# RoboCore_Light_sensor_bar.net
KiCad netlist of a schematic drawn in EAGLE
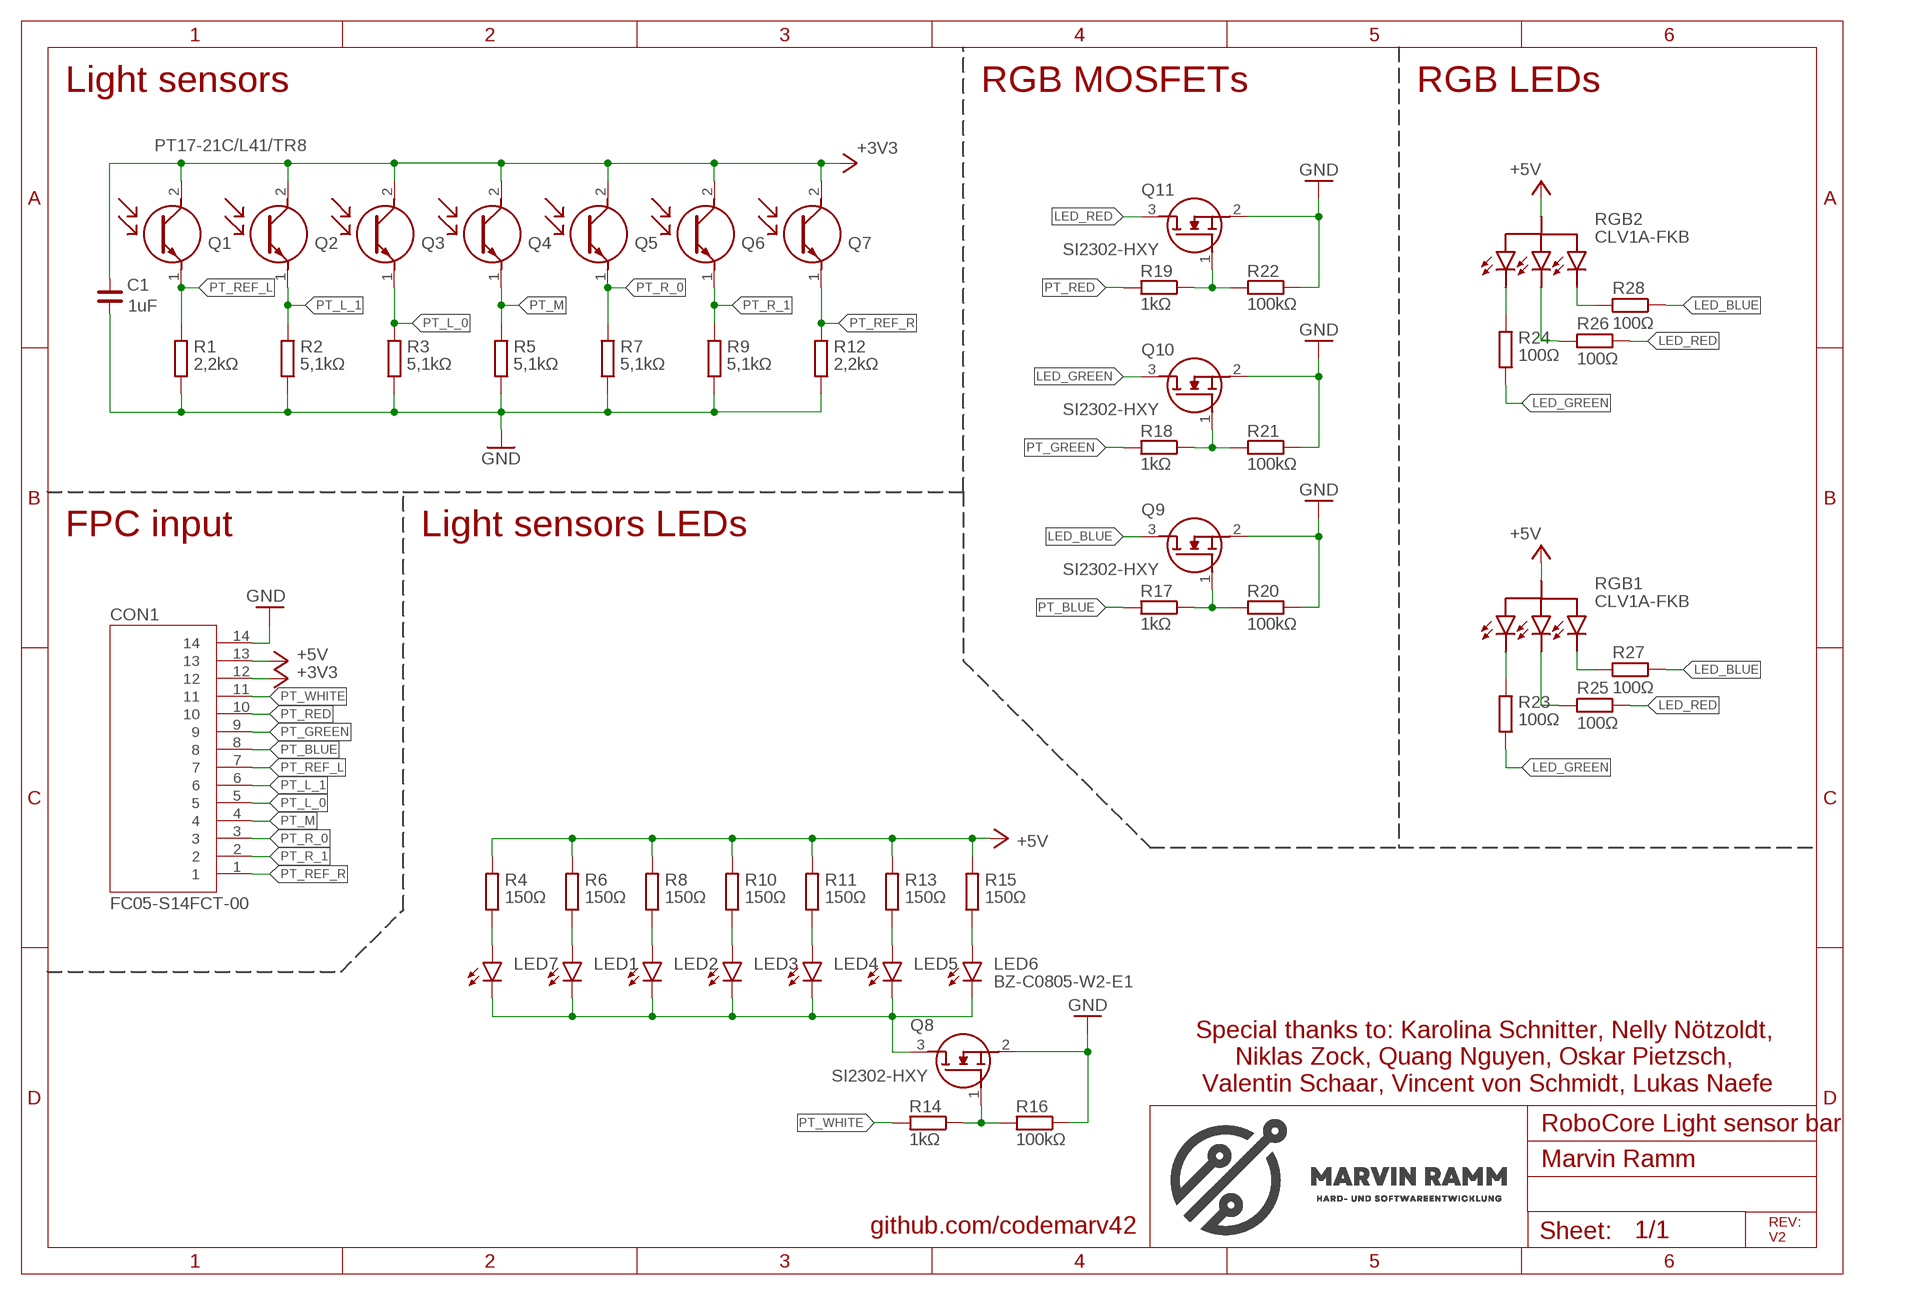
[diagram p0: schematic, sheet 1]

(export (version "E")
  (design (tool "Eeschema 10.0.6"))
  (components
    (comp (ref "C1")
      (value "1uF")
      (footprint "eagle-import:C0402")
      (libsource (lib "eagle-import") (part "C_0402"))
    )
    (comp (ref "CON1")
      (value "FC05-S14FCT-00")
      (footprint "eagle-import:FC05-S14FCT-00")
      (libsource (lib "eagle-import") (part "FC05-S14FCT-00"))
    )
    (comp (ref "LED1")
      (value "LEDCHIP-LED0805")
      (footprint "eagle-import:CHIP-LED0805")
      (libsource (lib "eagle-import") (part "LEDCHIP-LED0805"))
    )
    (comp (ref "LED2")
      (value "LEDCHIP-LED0805")
      (footprint "eagle-import:CHIP-LED0805")
      (libsource (lib "eagle-import") (part "LEDCHIP-LED0805"))
    )
    (comp (ref "LED3")
      (value "LEDCHIP-LED0805")
      (footprint "eagle-import:CHIP-LED0805")
      (libsource (lib "eagle-import") (part "LEDCHIP-LED0805"))
    )
    (comp (ref "LED4")
      (value "LEDCHIP-LED0805")
      (footprint "eagle-import:CHIP-LED0805")
      (libsource (lib "eagle-import") (part "LEDCHIP-LED0805"))
    )
    (comp (ref "LED5")
      (value "LEDCHIP-LED0805")
      (footprint "eagle-import:CHIP-LED0805")
      (libsource (lib "eagle-import") (part "LEDCHIP-LED0805"))
    )
    (comp (ref "LED6")
      (value "LEDCHIP-LED0805")
      (footprint "eagle-import:CHIP-LED0805")
      (libsource (lib "eagle-import") (part "LEDCHIP-LED0805"))
    )
    (comp (ref "LED7")
      (value "LEDCHIP-LED0805")
      (footprint "eagle-import:CHIP-LED0805")
      (libsource (lib "eagle-import") (part "LEDCHIP-LED0805"))
    )
    (comp (ref "Q1")
      (value "PT17-21C/L41/TR8")
      (footprint "eagle-import:0805")
      (libsource (lib "eagle-import") (part "PT17-21C/L41/TR8"))
    )
    (comp (ref "Q2")
      (value "PT17-21C/L41/TR8")
      (footprint "eagle-import:0805")
      (libsource (lib "eagle-import") (part "PT17-21C/L41/TR8"))
    )
    (comp (ref "Q3")
      (value "PT17-21C/L41/TR8")
      (footprint "eagle-import:0805")
      (libsource (lib "eagle-import") (part "PT17-21C/L41/TR8"))
    )
    (comp (ref "Q4")
      (value "PT17-21C/L41/TR8")
      (footprint "eagle-import:0805")
      (libsource (lib "eagle-import") (part "PT17-21C/L41/TR8"))
    )
    (comp (ref "Q5")
      (value "PT17-21C/L41/TR8")
      (footprint "eagle-import:0805")
      (libsource (lib "eagle-import") (part "PT17-21C/L41/TR8"))
    )
    (comp (ref "Q6")
      (value "PT17-21C/L41/TR8")
      (footprint "eagle-import:0805")
      (libsource (lib "eagle-import") (part "PT17-21C/L41/TR8"))
    )
    (comp (ref "Q7")
      (value "PT17-21C/L41/TR8")
      (footprint "eagle-import:0805")
      (libsource (lib "eagle-import") (part "PT17-21C/L41/TR8"))
    )
    (comp (ref "Q8")
      (value "SI2302DDS-T1-GE3")
      (footprint "eagle-import:SOT95P237X112-3N")
      (fields (field (name "MOUSER_PART_NUMBER") "78-SI2302DDS-T1-GE3"))
      (libsource (lib "eagle-import") (part "SI2302DDS-T1-GE3"))
    )
    (comp (ref "Q9")
      (value "SI2302DDS-T1-GE3")
      (footprint "eagle-import:SOT95P237X112-3N")
      (fields (field (name "MOUSER_PART_NUMBER") "78-SI2302DDS-T1-GE3"))
      (libsource (lib "eagle-import") (part "SI2302DDS-T1-GE3"))
    )
    (comp (ref "Q10")
      (value "SI2302DDS-T1-GE3")
      (footprint "eagle-import:SOT95P237X112-3N")
      (fields (field (name "MOUSER_PART_NUMBER") "78-SI2302DDS-T1-GE3"))
      (libsource (lib "eagle-import") (part "SI2302DDS-T1-GE3"))
    )
    (comp (ref "Q11")
      (value "SI2302DDS-T1-GE3")
      (footprint "eagle-import:SOT95P237X112-3N")
      (fields (field (name "MOUSER_PART_NUMBER") "78-SI2302DDS-T1-GE3"))
      (libsource (lib "eagle-import") (part "SI2302DDS-T1-GE3"))
    )
    (comp (ref "R1")
      (value "2,2kΩ")
      (footprint "eagle-import:R0402")
      (libsource (lib "eagle-import") (part "R_0402"))
    )
    (comp (ref "R2")
      (value "5,1kΩ")
      (footprint "eagle-import:R0402")
      (libsource (lib "eagle-import") (part "R_0402"))
    )
    (comp (ref "R3")
      (value "5,1kΩ")
      (footprint "eagle-import:R0402")
      (libsource (lib "eagle-import") (part "R_0402"))
    )
    (comp (ref "R4")
      (value "150Ω")
      (footprint "eagle-import:R0402")
      (libsource (lib "eagle-import") (part "R_0402"))
    )
    (comp (ref "R5")
      (value "5,1kΩ")
      (footprint "eagle-import:R0402")
      (libsource (lib "eagle-import") (part "R_0402"))
    )
    (comp (ref "R6")
      (value "150Ω")
      (footprint "eagle-import:R0402")
      (libsource (lib "eagle-import") (part "R_0402"))
    )
    (comp (ref "R7")
      (value "5,1kΩ")
      (footprint "eagle-import:R0402")
      (libsource (lib "eagle-import") (part "R_0402"))
    )
    (comp (ref "R8")
      (value "150Ω")
      (footprint "eagle-import:R0402")
      (libsource (lib "eagle-import") (part "R_0402"))
    )
    (comp (ref "R9")
      (value "5,1kΩ")
      (footprint "eagle-import:R0402")
      (libsource (lib "eagle-import") (part "R_0402"))
    )
    (comp (ref "R10")
      (value "150Ω")
      (footprint "eagle-import:R0402")
      (libsource (lib "eagle-import") (part "R_0402"))
    )
    (comp (ref "R11")
      (value "150Ω")
      (footprint "eagle-import:R0402")
      (libsource (lib "eagle-import") (part "R_0402"))
    )
    (comp (ref "R12")
      (value "2,2kΩ")
      (footprint "eagle-import:R0402")
      (libsource (lib "eagle-import") (part "R_0402"))
    )
    (comp (ref "R13")
      (value "150Ω")
      (footprint "eagle-import:R0402")
      (libsource (lib "eagle-import") (part "R_0402"))
    )
    (comp (ref "R14")
      (value "1kΩ")
      (footprint "eagle-import:R0402")
      (libsource (lib "eagle-import") (part "R_0402"))
    )
    (comp (ref "R15")
      (value "150Ω")
      (footprint "eagle-import:R0402")
      (libsource (lib "eagle-import") (part "R_0402"))
    )
    (comp (ref "R16")
      (value "100kΩ")
      (footprint "eagle-import:R0402")
      (libsource (lib "eagle-import") (part "R_0402"))
    )
    (comp (ref "R17")
      (value "1kΩ")
      (footprint "eagle-import:R0402")
      (libsource (lib "eagle-import") (part "R_0402"))
    )
    (comp (ref "R18")
      (value "1kΩ")
      (footprint "eagle-import:R0402")
      (libsource (lib "eagle-import") (part "R_0402"))
    )
    (comp (ref "R19")
      (value "1kΩ")
      (footprint "eagle-import:R0402")
      (libsource (lib "eagle-import") (part "R_0402"))
    )
    (comp (ref "R20")
      (value "100kΩ")
      (footprint "eagle-import:R0402")
      (libsource (lib "eagle-import") (part "R_0402"))
    )
    (comp (ref "R21")
      (value "100kΩ")
      (footprint "eagle-import:R0402")
      (libsource (lib "eagle-import") (part "R_0402"))
    )
    (comp (ref "R22")
      (value "100kΩ")
      (footprint "eagle-import:R0402")
      (libsource (lib "eagle-import") (part "R_0402"))
    )
    (comp (ref "R23")
      (value "100Ω")
      (footprint "eagle-import:R0402")
      (libsource (lib "eagle-import") (part "R_0402"))
    )
    (comp (ref "R24")
      (value "100Ω")
      (footprint "eagle-import:R0402")
      (libsource (lib "eagle-import") (part "R_0402"))
    )
    (comp (ref "R25")
      (value "100Ω")
      (footprint "eagle-import:R0402")
      (libsource (lib "eagle-import") (part "R_0402"))
    )
    (comp (ref "R26")
      (value "100Ω")
      (footprint "eagle-import:R0402")
      (libsource (lib "eagle-import") (part "R_0402"))
    )
    (comp (ref "R27")
      (value "100Ω")
      (footprint "eagle-import:R0402")
      (libsource (lib "eagle-import") (part "R_0402"))
    )
    (comp (ref "R28")
      (value "100Ω")
      (footprint "eagle-import:R0402")
      (libsource (lib "eagle-import") (part "R_0402"))
    )
    (comp (ref "RGB1")
      (value "RGBLED")
      (footprint "eagle-import:RGBLED")
      (libsource (lib "eagle-import") (part "RGBLED"))
    )
    (comp (ref "RGB2")
      (value "RGBLED")
      (footprint "eagle-import:RGBLED")
      (libsource (lib "eagle-import") (part "RGBLED"))
    )
  )
  (nets
    (net (code "1") (name "+3V3") (class "Default")
      (node (ref "C1") (pin "2") (pinfunction "2_2") (pintype "passive"))
      (node (ref "CON1") (pin "12") (pinfunction "12_12") (pintype "bidirectional"))
      (node (ref "Q1") (pin "2") (pinfunction "C_2") (pintype "bidirectional"))
      (node (ref "Q2") (pin "2") (pinfunction "C_2") (pintype "bidirectional"))
      (node (ref "Q3") (pin "2") (pinfunction "C_2") (pintype "bidirectional"))
      (node (ref "Q4") (pin "2") (pinfunction "C_2") (pintype "bidirectional"))
      (node (ref "Q5") (pin "2") (pinfunction "C_2") (pintype "bidirectional"))
      (node (ref "Q6") (pin "2") (pinfunction "C_2") (pintype "bidirectional"))
      (node (ref "Q7") (pin "2") (pinfunction "C_2") (pintype "bidirectional"))
    )
    (net (code "2") (name "+5V") (class "Default")
      (node (ref "CON1") (pin "13") (pinfunction "13_13") (pintype "bidirectional"))
      (node (ref "R10") (pin "1") (pinfunction "1_1") (pintype "passive"))
      (node (ref "R11") (pin "1") (pinfunction "1_1") (pintype "passive"))
      (node (ref "R13") (pin "1") (pinfunction "1_1") (pintype "passive"))
      (node (ref "R15") (pin "1") (pinfunction "1_1") (pintype "passive"))
      (node (ref "R4") (pin "1") (pinfunction "1_1") (pintype "passive"))
      (node (ref "R6") (pin "1") (pinfunction "1_1") (pintype "passive"))
      (node (ref "R8") (pin "1") (pinfunction "1_1") (pintype "passive"))
      (node (ref "RGB1") (pin "+5V") (pinfunction "+5V_+5V") (pintype "bidirectional"))
      (node (ref "RGB2") (pin "+5V") (pinfunction "+5V_+5V") (pintype "bidirectional"))
    )
    (net (code "3") (name "GND") (class "Default")
      (node (ref "C1") (pin "1") (pinfunction "1_1") (pintype "passive"))
      (node (ref "CON1") (pin "14") (pinfunction "14_14") (pintype "bidirectional"))
      (node (ref "Q10") (pin "2") (pinfunction "S_2") (pintype "bidirectional"))
      (node (ref "Q11") (pin "2") (pinfunction "S_2") (pintype "bidirectional"))
      (node (ref "Q8") (pin "2") (pinfunction "S_2") (pintype "bidirectional"))
      (node (ref "Q9") (pin "2") (pinfunction "S_2") (pintype "bidirectional"))
      (node (ref "R1") (pin "2") (pinfunction "2_2") (pintype "passive"))
      (node (ref "R12") (pin "2") (pinfunction "2_2") (pintype "passive"))
      (node (ref "R16") (pin "2") (pinfunction "2_2") (pintype "passive"))
      (node (ref "R2") (pin "2") (pinfunction "2_2") (pintype "passive"))
      (node (ref "R20") (pin "2") (pinfunction "2_2") (pintype "passive"))
      (node (ref "R21") (pin "2") (pinfunction "2_2") (pintype "passive"))
      (node (ref "R22") (pin "2") (pinfunction "2_2") (pintype "passive"))
      (node (ref "R3") (pin "2") (pinfunction "2_2") (pintype "passive"))
      (node (ref "R5") (pin "2") (pinfunction "2_2") (pintype "passive"))
      (node (ref "R7") (pin "2") (pinfunction "2_2") (pintype "passive"))
      (node (ref "R9") (pin "2") (pinfunction "2_2") (pintype "passive"))
    )
    (net (code "4") (name "LED_BLUE") (class "Default")
      (node (ref "Q9") (pin "3") (pinfunction "D_3") (pintype "bidirectional"))
      (node (ref "R27") (pin "2") (pinfunction "2_2") (pintype "passive"))
      (node (ref "R28") (pin "2") (pinfunction "2_2") (pintype "passive"))
    )
    (net (code "5") (name "LED_GREEN") (class "Default")
      (node (ref "Q10") (pin "3") (pinfunction "D_3") (pintype "bidirectional"))
      (node (ref "R23") (pin "2") (pinfunction "2_2") (pintype "passive"))
      (node (ref "R24") (pin "2") (pinfunction "2_2") (pintype "passive"))
    )
    (net (code "6") (name "LED_RED") (class "Default")
      (node (ref "Q11") (pin "3") (pinfunction "D_3") (pintype "bidirectional"))
      (node (ref "R25") (pin "2") (pinfunction "2_2") (pintype "passive"))
      (node (ref "R26") (pin "2") (pinfunction "2_2") (pintype "passive"))
    )
    (net (code "7") (name "Net-(LED1-PadA)") (class "Default")
      (node (ref "LED1") (pin "A") (pinfunction "A_A") (pintype "passive"))
      (node (ref "R6") (pin "2") (pinfunction "2_2") (pintype "passive"))
    )
    (net (code "8") (name "Net-(LED2-PadA)") (class "Default")
      (node (ref "LED2") (pin "A") (pinfunction "A_A") (pintype "passive"))
      (node (ref "R8") (pin "2") (pinfunction "2_2") (pintype "passive"))
    )
    (net (code "9") (name "Net-(LED3-PadA)") (class "Default")
      (node (ref "LED3") (pin "A") (pinfunction "A_A") (pintype "passive"))
      (node (ref "R10") (pin "2") (pinfunction "2_2") (pintype "passive"))
    )
    (net (code "10") (name "Net-(LED4-PadA)") (class "Default")
      (node (ref "LED4") (pin "A") (pinfunction "A_A") (pintype "passive"))
      (node (ref "R11") (pin "2") (pinfunction "2_2") (pintype "passive"))
    )
    (net (code "11") (name "Net-(LED5-PadA)") (class "Default")
      (node (ref "LED5") (pin "A") (pinfunction "A_A") (pintype "passive"))
      (node (ref "R13") (pin "2") (pinfunction "2_2") (pintype "passive"))
    )
    (net (code "12") (name "Net-(LED6-PadA)") (class "Default")
      (node (ref "LED6") (pin "A") (pinfunction "A_A") (pintype "passive"))
      (node (ref "R15") (pin "2") (pinfunction "2_2") (pintype "passive"))
    )
    (net (code "13") (name "Net-(LED7-PadA)") (class "Default")
      (node (ref "LED7") (pin "A") (pinfunction "A_A") (pintype "passive"))
      (node (ref "R4") (pin "2") (pinfunction "2_2") (pintype "passive"))
    )
    (net (code "14") (name "Net-(Q8-D)") (class "Default")
      (node (ref "LED1") (pin "C") (pinfunction "C_C") (pintype "passive"))
      (node (ref "LED2") (pin "C") (pinfunction "C_C") (pintype "passive"))
      (node (ref "LED3") (pin "C") (pinfunction "C_C") (pintype "passive"))
      (node (ref "LED4") (pin "C") (pinfunction "C_C") (pintype "passive"))
      (node (ref "LED5") (pin "C") (pinfunction "C_C") (pintype "passive"))
      (node (ref "LED6") (pin "C") (pinfunction "C_C") (pintype "passive"))
      (node (ref "LED7") (pin "C") (pinfunction "C_C") (pintype "passive"))
      (node (ref "Q8") (pin "3") (pinfunction "D_3") (pintype "bidirectional"))
    )
    (net (code "15") (name "Net-(Q8-G)") (class "Default")
      (node (ref "Q8") (pin "1") (pinfunction "G_1") (pintype "bidirectional"))
      (node (ref "R14") (pin "2") (pinfunction "2_2") (pintype "passive"))
      (node (ref "R16") (pin "1") (pinfunction "1_1") (pintype "passive"))
    )
    (net (code "16") (name "Net-(Q9-G)") (class "Default")
      (node (ref "Q9") (pin "1") (pinfunction "G_1") (pintype "bidirectional"))
      (node (ref "R17") (pin "2") (pinfunction "2_2") (pintype "passive"))
      (node (ref "R20") (pin "1") (pinfunction "1_1") (pintype "passive"))
    )
    (net (code "17") (name "Net-(Q10-G)") (class "Default")
      (node (ref "Q10") (pin "1") (pinfunction "G_1") (pintype "bidirectional"))
      (node (ref "R18") (pin "2") (pinfunction "2_2") (pintype "passive"))
      (node (ref "R21") (pin "1") (pinfunction "1_1") (pintype "passive"))
    )
    (net (code "18") (name "Net-(Q11-G)") (class "Default")
      (node (ref "Q11") (pin "1") (pinfunction "G_1") (pintype "bidirectional"))
      (node (ref "R19") (pin "2") (pinfunction "2_2") (pintype "passive"))
      (node (ref "R22") (pin "1") (pinfunction "1_1") (pintype "passive"))
    )
    (net (code "19") (name "Net-(R23-Pad1)") (class "Default")
      (node (ref "R23") (pin "1") (pinfunction "1_1") (pintype "passive"))
      (node (ref "RGB1") (pin "P3") (pinfunction "P3_P3") (pintype "bidirectional"))
    )
    (net (code "20") (name "Net-(R24-Pad1)") (class "Default")
      (node (ref "R24") (pin "1") (pinfunction "1_1") (pintype "passive"))
      (node (ref "RGB2") (pin "P3") (pinfunction "P3_P3") (pintype "bidirectional"))
    )
    (net (code "21") (name "Net-(R25-Pad1)") (class "Default")
      (node (ref "R25") (pin "1") (pinfunction "1_1") (pintype "passive"))
      (node (ref "RGB1") (pin "P2") (pinfunction "P2_P2") (pintype "bidirectional"))
    )
    (net (code "22") (name "Net-(R26-Pad1)") (class "Default")
      (node (ref "R26") (pin "1") (pinfunction "1_1") (pintype "passive"))
      (node (ref "RGB2") (pin "P2") (pinfunction "P2_P2") (pintype "bidirectional"))
    )
    (net (code "23") (name "Net-(R27-Pad1)") (class "Default")
      (node (ref "R27") (pin "1") (pinfunction "1_1") (pintype "passive"))
      (node (ref "RGB1") (pin "P1") (pinfunction "P1_P1") (pintype "bidirectional"))
    )
    (net (code "24") (name "Net-(R28-Pad1)") (class "Default")
      (node (ref "R28") (pin "1") (pinfunction "1_1") (pintype "passive"))
      (node (ref "RGB2") (pin "P1") (pinfunction "P1_P1") (pintype "bidirectional"))
    )
    (net (code "25") (name "PT_BLUE") (class "Default")
      (node (ref "CON1") (pin "8") (pinfunction "8_8") (pintype "bidirectional"))
      (node (ref "R17") (pin "1") (pinfunction "1_1") (pintype "passive"))
    )
    (net (code "26") (name "PT_GREEN") (class "Default")
      (node (ref "CON1") (pin "9") (pinfunction "9_9") (pintype "bidirectional"))
      (node (ref "R18") (pin "1") (pinfunction "1_1") (pintype "passive"))
    )
    (net (code "27") (name "PT_L_0") (class "Default")
      (node (ref "CON1") (pin "5") (pinfunction "5_5") (pintype "bidirectional"))
      (node (ref "Q3") (pin "1") (pinfunction "E_1") (pintype "bidirectional"))
      (node (ref "R3") (pin "1") (pinfunction "1_1") (pintype "passive"))
    )
    (net (code "28") (name "PT_L_1") (class "Default")
      (node (ref "CON1") (pin "6") (pinfunction "6_6") (pintype "bidirectional"))
      (node (ref "Q2") (pin "1") (pinfunction "E_1") (pintype "bidirectional"))
      (node (ref "R2") (pin "1") (pinfunction "1_1") (pintype "passive"))
    )
    (net (code "29") (name "PT_M") (class "Default")
      (node (ref "CON1") (pin "4") (pinfunction "4_4") (pintype "bidirectional"))
      (node (ref "Q4") (pin "1") (pinfunction "E_1") (pintype "bidirectional"))
      (node (ref "R5") (pin "1") (pinfunction "1_1") (pintype "passive"))
    )
    (net (code "30") (name "PT_RED") (class "Default")
      (node (ref "CON1") (pin "10") (pinfunction "10_10") (pintype "bidirectional"))
      (node (ref "R19") (pin "1") (pinfunction "1_1") (pintype "passive"))
    )
    (net (code "31") (name "PT_REF_L") (class "Default")
      (node (ref "CON1") (pin "7") (pinfunction "7_7") (pintype "bidirectional"))
      (node (ref "Q1") (pin "1") (pinfunction "E_1") (pintype "bidirectional"))
      (node (ref "R1") (pin "1") (pinfunction "1_1") (pintype "passive"))
    )
    (net (code "32") (name "PT_REF_R") (class "Default")
      (node (ref "CON1") (pin "1") (pinfunction "1_1") (pintype "bidirectional"))
      (node (ref "Q7") (pin "1") (pinfunction "E_1") (pintype "bidirectional"))
      (node (ref "R12") (pin "1") (pinfunction "1_1") (pintype "passive"))
    )
    (net (code "33") (name "PT_R_0") (class "Default")
      (node (ref "CON1") (pin "3") (pinfunction "3_3") (pintype "bidirectional"))
      (node (ref "Q5") (pin "1") (pinfunction "E_1") (pintype "bidirectional"))
      (node (ref "R7") (pin "1") (pinfunction "1_1") (pintype "passive"))
    )
    (net (code "34") (name "PT_R_1") (class "Default")
      (node (ref "CON1") (pin "2") (pinfunction "2_2") (pintype "bidirectional"))
      (node (ref "Q6") (pin "1") (pinfunction "E_1") (pintype "bidirectional"))
      (node (ref "R9") (pin "1") (pinfunction "1_1") (pintype "passive"))
    )
    (net (code "35") (name "PT_WHITE") (class "Default")
      (node (ref "CON1") (pin "11") (pinfunction "11_11") (pintype "bidirectional"))
      (node (ref "R14") (pin "1") (pinfunction "1_1") (pintype "passive"))
    )
  )
)
